# motordriver-v5_1_demux_dribbler.net
KiCad netlist of a schematic drawn in Altium Designer
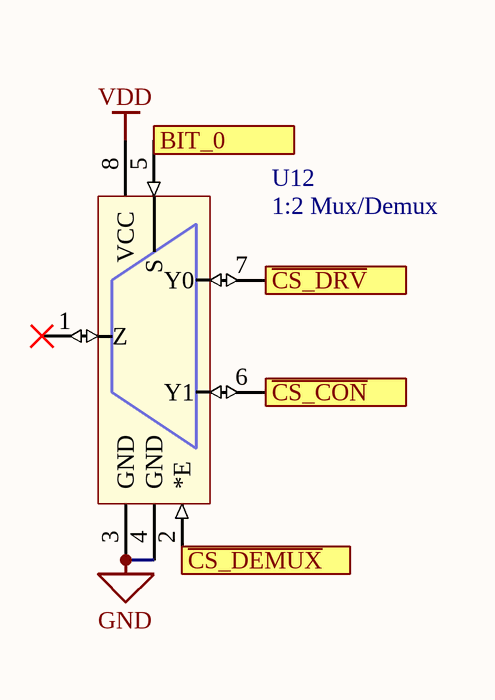
[diagram p0: motordriver-v5.1_demux_dribbler.SchDoc]

(export (version "E")
  (design (tool "Eeschema 10.0.6"))
  (components
    (comp (ref "U12")
      (value "1:2 Mux/Demux")
      (footprint "TSOP65P400X110-8N")
      (description "74LVC Series 5.5 V SMT 2-Channel Analog Multiplexer/Demultiplexer - TSSOP-8")
      (fields (field (name "PART NUMBER") "74LVC1G53DP,125"))
      (libsource (lib "IC_Library") (part "74LVC1G53DP,125"))
    )
  )
  (nets
    (net (code "1") (name "/BIT_0") (class "Default")
      (node (ref "U12") (pin "5") (pinfunction "S_5") (pintype "input"))
    )
    (net (code "2") (name "/~{CS_CON}") (class "Default")
      (node (ref "U12") (pin "6") (pinfunction "Y1_6") (pintype "bidirectional"))
    )
    (net (code "3") (name "/~{CS_DEMUX}") (class "Default")
      (node (ref "U12") (pin "2") (pinfunction "*E_2") (pintype "input"))
    )
    (net (code "4") (name "/~{CS_DRV}") (class "Default")
      (node (ref "U12") (pin "7") (pinfunction "Y0_7") (pintype "bidirectional"))
    )
    (net (code "5") (name "GND") (class "Default")
      (node (ref "U12") (pin "3") (pinfunction "GND_3") (pintype "passive"))
      (node (ref "U12") (pin "4") (pinfunction "GND_4") (pintype "passive"))
    )
    (net (code "6") (name "VDD") (class "Default")
      (node (ref "U12") (pin "8") (pinfunction "VCC_8") (pintype "power_in"))
    )
    (net (code "7") (name "unconnected-(U12-Z-Pad1)") (class "Default")
      (node (ref "U12") (pin "1") (pinfunction "Z_1") (pintype "bidirectional+no_connect"))
    )
  )
)
